# r_gulateur.net
KiCad netlist of a schematic drawn in Altium Designer
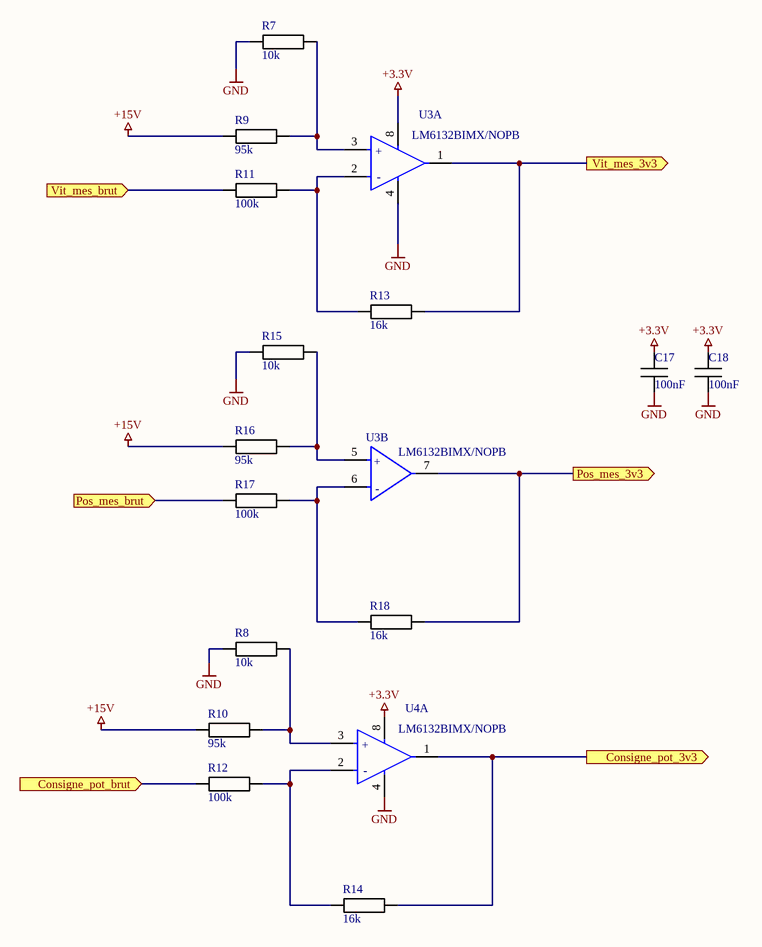
[diagram p0: régulateur.SchDoc]

(export (version "E")
  (design (tool "Eeschema 10.0.6"))
  (components
    (comp (ref "C17")
      (value "100nF")
      (footprint "CAPC1608X08M")
      (description "CAPC 100nF X7R 50V 10% 1608 (0603 INCH)")
      (fields (field (name "VOLTAGE") "50V") (field (name "MANUFACTURER") "TDK"))
      (libsource (lib "ETML-ES") (part "CAP"))
    )
    (comp (ref "C18")
      (value "100nF")
      (footprint "CAPC1608X08M")
      (description "CAPC 100nF X7R 50V 10% 1608 (0603 INCH)")
      (fields (field (name "VOLTAGE") "50V") (field (name "MANUFACTURER") "TDK"))
      (libsource (lib "ETML-ES") (part "CAP"))
    )
    (comp (ref "R7")
      (value "10k")
      (footprint "RESC2012X06M")
      (description "RES 68kohm  ±1% 0.125W 2012 (0805 INCH)")
      (fields (field (name "MANUFACTURER") "Yageo") (field (name "VOLTAGE") "150V"))
      (libsource (lib "ETML-ES") (part "RES"))
    )
    (comp (ref "R8")
      (value "10k")
      (footprint "RESC2012X06M")
      (description "RES 68kohm  ±1% 0.125W 2012 (0805 INCH)")
      (fields (field (name "MANUFACTURER") "Yageo") (field (name "VOLTAGE") "150V"))
      (libsource (lib "ETML-ES") (part "RES"))
    )
    (comp (ref "R9")
      (value "95k")
      (footprint "RESC2012X06M")
      (description "RES 68kohm  ±1% 0.125W 2012 (0805 INCH)")
      (fields (field (name "MANUFACTURER") "Yageo") (field (name "VOLTAGE") "150V"))
      (libsource (lib "ETML-ES") (part "RES"))
    )
    (comp (ref "R10")
      (value "95k")
      (footprint "RESC2012X06M")
      (description "RES 68kohm  ±1% 0.125W 2012 (0805 INCH)")
      (fields (field (name "MANUFACTURER") "Yageo") (field (name "VOLTAGE") "150V"))
      (libsource (lib "ETML-ES") (part "RES"))
    )
    (comp (ref "R11")
      (value "100k")
      (footprint "RESC2012X06M")
      (description "RES 68kohm  ±1% 0.125W 2012 (0805 INCH)")
      (fields (field (name "MANUFACTURER") "Yageo") (field (name "VOLTAGE") "150V"))
      (libsource (lib "ETML-ES") (part "RES"))
    )
    (comp (ref "R12")
      (value "100k")
      (footprint "RESC2012X06M")
      (description "RES 68kohm  ±1% 0.125W 2012 (0805 INCH)")
      (fields (field (name "MANUFACTURER") "Yageo") (field (name "VOLTAGE") "150V"))
      (libsource (lib "ETML-ES") (part "RES"))
    )
    (comp (ref "R13")
      (value "16k")
      (footprint "RESC2012X06M")
      (description "RES 68kohm  ±1% 0.125W 2012 (0805 INCH)")
      (fields (field (name "MANUFACTURER") "Yageo") (field (name "VOLTAGE") "150V"))
      (libsource (lib "ETML-ES") (part "RES"))
    )
    (comp (ref "R14")
      (value "16k")
      (footprint "RESC2012X06M")
      (description "RES 68kohm  ±1% 0.125W 2012 (0805 INCH)")
      (fields (field (name "MANUFACTURER") "Yageo") (field (name "VOLTAGE") "150V"))
      (libsource (lib "ETML-ES") (part "RES"))
    )
    (comp (ref "R15")
      (value "10k")
      (footprint "RESC2012X06M")
      (description "RES 68kohm  ±1% 0.125W 2012 (0805 INCH)")
      (fields (field (name "MANUFACTURER") "Yageo") (field (name "VOLTAGE") "150V"))
      (libsource (lib "ETML-ES") (part "RES"))
    )
    (comp (ref "R16")
      (value "95k")
      (footprint "RESC2012X06M")
      (description "RES 68kohm  ±1% 0.125W 2012 (0805 INCH)")
      (fields (field (name "MANUFACTURER") "Yageo") (field (name "VOLTAGE") "150V"))
      (libsource (lib "ETML-ES") (part "RES"))
    )
    (comp (ref "R17")
      (value "100k")
      (footprint "RESC2012X06M")
      (description "RES 68kohm  ±1% 0.125W 2012 (0805 INCH)")
      (fields (field (name "MANUFACTURER") "Yageo") (field (name "VOLTAGE") "150V"))
      (libsource (lib "ETML-ES") (part "RES"))
    )
    (comp (ref "R18")
      (value "16k")
      (footprint "RESC2012X06M")
      (description "RES 68kohm  ±1% 0.125W 2012 (0805 INCH)")
      (fields (field (name "MANUFACTURER") "Yageo") (field (name "VOLTAGE") "150V"))
      (libsource (lib "ETML-ES") (part "RES"))
    )
    (comp (ref "U3")
      (value "LM6132BIMX/NOPB")
      (footprint "FP-LM6132BIMX-NOPB-MFG")
      (description "IC OPAMP GP 2 CIRCUIT 8SOIC")
      (fields
        (field (name "MANUFACTURER") "Texas Instruments")
        (field (name "OCTOPART") "https://octopart.com/lm6132bimx%2Fnopb-texas+instruments-24814947")
      )
      (libsource (lib "Altium Content Vault") (part "499df5fc91ff7ad023bcaf249d8becd"))
    )
    (comp (ref "U4")
      (value "LM6132BIMX/NOPB")
      (footprint "FP-LM6132BIMX-NOPB-MFG")
      (description "IC OPAMP GP 2 CIRCUIT 8SOIC")
      (fields
        (field (name "MANUFACTURER") "Texas Instruments")
        (field (name "OCTOPART") "https://octopart.com/lm6132bimx%2Fnopb-texas+instruments-24814947")
      )
      (libsource (lib "Altium Content Vault") (part "499df5fc91ff7ad023bcaf249d8becd"))
    )
  )
  (nets
    (net (code "1") (name "+3.3V") (class "Default")
      (node (ref "C17") (pin "2") (pinfunction "2_2") (pintype "passive"))
      (node (ref "C18") (pin "2") (pinfunction "2_2") (pintype "passive"))
      (node (ref "U3") (pin "8") (pinfunction "V+_8") (pintype "power_in"))
      (node (ref "U4") (pin "8") (pinfunction "V+_8") (pintype "power_in"))
    )
    (net (code "2") (name "+15V") (class "Default")
      (node (ref "R10") (pin "1") (pinfunction "1_1") (pintype "passive"))
      (node (ref "R16") (pin "1") (pinfunction "1_1") (pintype "passive"))
      (node (ref "R9") (pin "1") (pinfunction "1_1") (pintype "passive"))
    )
    (net (code "3") (name "/Consigne_pot_3v3") (class "Default")
      (node (ref "R14") (pin "1") (pinfunction "1_1") (pintype "passive"))
      (node (ref "U4") (pin "1") (pinfunction "OUT_A_1") (pintype "passive"))
    )
    (net (code "4") (name "/Consigne_pot_brut") (class "Default")
      (node (ref "R12") (pin "1") (pinfunction "1_1") (pintype "passive"))
    )
    (net (code "5") (name "/Pos_mes_3v3") (class "Default")
      (node (ref "R18") (pin "1") (pinfunction "1_1") (pintype "passive"))
      (node (ref "U3") (pin "7") (pinfunction "OUT_B_7") (pintype "passive"))
    )
    (net (code "6") (name "/Pos_mes_brut") (class "Default")
      (node (ref "R17") (pin "1") (pinfunction "1_1") (pintype "passive"))
    )
    (net (code "7") (name "/Vit_mes_3v3") (class "Default")
      (node (ref "R13") (pin "1") (pinfunction "1_1") (pintype "passive"))
      (node (ref "U3") (pin "1") (pinfunction "OUT_A_1") (pintype "passive"))
    )
    (net (code "8") (name "/Vit_mes_brut") (class "Default")
      (node (ref "R11") (pin "1") (pinfunction "1_1") (pintype "passive"))
    )
    (net (code "9") (name "GND") (class "Default")
      (node (ref "C17") (pin "1") (pinfunction "1_1") (pintype "passive"))
      (node (ref "C18") (pin "1") (pinfunction "1_1") (pintype "passive"))
      (node (ref "R15") (pin "1") (pinfunction "1_1") (pintype "passive"))
      (node (ref "R7") (pin "1") (pinfunction "1_1") (pintype "passive"))
      (node (ref "R8") (pin "1") (pinfunction "1_1") (pintype "passive"))
      (node (ref "U3") (pin "4") (pinfunction "V-_4") (pintype "power_in"))
      (node (ref "U4") (pin "4") (pinfunction "V-_4") (pintype "power_in"))
    )
    (net (code "10") (name "Net-(U3A-+IN_A)") (class "Default")
      (node (ref "R7") (pin "2") (pinfunction "2_2") (pintype "passive"))
      (node (ref "R9") (pin "2") (pinfunction "2_2") (pintype "passive"))
      (node (ref "U3") (pin "3") (pinfunction "+IN_A_3") (pintype "tri_state"))
    )
    (net (code "11") (name "Net-(U3A--IN_A)") (class "Default")
      (node (ref "R11") (pin "2") (pinfunction "2_2") (pintype "passive"))
      (node (ref "R13") (pin "2") (pinfunction "2_2") (pintype "passive"))
      (node (ref "U3") (pin "2") (pinfunction "-IN_A_2") (pintype "tri_state"))
    )
    (net (code "12") (name "Net-(U3B-+IN_B)") (class "Default")
      (node (ref "R15") (pin "2") (pinfunction "2_2") (pintype "passive"))
      (node (ref "R16") (pin "2") (pinfunction "2_2") (pintype "passive"))
      (node (ref "U3") (pin "5") (pinfunction "+IN_B_5") (pintype "tri_state"))
    )
    (net (code "13") (name "Net-(U3B--IN_B)") (class "Default")
      (node (ref "R17") (pin "2") (pinfunction "2_2") (pintype "passive"))
      (node (ref "R18") (pin "2") (pinfunction "2_2") (pintype "passive"))
      (node (ref "U3") (pin "6") (pinfunction "-IN_B_6") (pintype "tri_state"))
    )
    (net (code "14") (name "Net-(U4A-+IN_A)") (class "Default")
      (node (ref "R10") (pin "2") (pinfunction "2_2") (pintype "passive"))
      (node (ref "R8") (pin "2") (pinfunction "2_2") (pintype "passive"))
      (node (ref "U4") (pin "3") (pinfunction "+IN_A_3") (pintype "tri_state"))
    )
    (net (code "15") (name "Net-(U4A--IN_A)") (class "Default")
      (node (ref "R12") (pin "2") (pinfunction "2_2") (pintype "passive"))
      (node (ref "R14") (pin "2") (pinfunction "2_2") (pintype "passive"))
      (node (ref "U4") (pin "2") (pinfunction "-IN_A_2") (pintype "tri_state"))
    )
  )
)
